# rgb_led.net
KiCad netlist of a schematic drawn in EAGLE
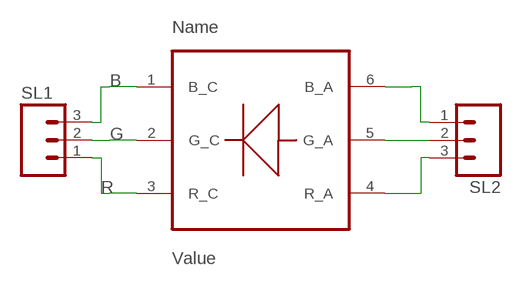
[diagram p0: schematic, sheet 1]

(export (version "E")
  (design (tool "Eeschema 10.0.6"))
  (components
    (comp (ref "SL1")
      (value "M03")
      (footprint "eagle-import:03P")
      (libsource (lib "eagle-import") (part "M03"))
    )
    (comp (ref "SL2")
      (value "M03")
      (footprint "eagle-import:03P")
      (libsource (lib "eagle-import") (part "M03"))
    )
    (comp (ref "U$2")
      (value "RGB_SMD_3W")
      (footprint "eagle-import:RGB_SMD_6PIN")
      (libsource (lib "eagle-import") (part "RGB_SMD_3W"))
    )
  )
  (nets
    (net (code "1") (name "/B") (class "Default")
      (node (ref "SL1") (pin "3") (pinfunction "3_3") (pintype "passive"))
      (node (ref "U$2") (pin "1") (pinfunction "B_C_1") (pintype "passive"))
    )
    (net (code "2") (name "/G") (class "Default")
      (node (ref "SL1") (pin "2") (pinfunction "2_2") (pintype "passive"))
      (node (ref "U$2") (pin "2") (pinfunction "G_C_2") (pintype "passive"))
    )
    (net (code "3") (name "/R") (class "Default")
      (node (ref "SL1") (pin "1") (pinfunction "1_1") (pintype "passive"))
      (node (ref "U$2") (pin "3") (pinfunction "R_C_3") (pintype "passive"))
    )
    (net (code "4") (name "Net-(U$2-B_A)") (class "Default")
      (node (ref "SL2") (pin "1") (pinfunction "1_1") (pintype "passive"))
      (node (ref "U$2") (pin "6") (pinfunction "B_A_6") (pintype "passive"))
    )
    (net (code "5") (name "Net-(U$2-G_A)") (class "Default")
      (node (ref "SL2") (pin "2") (pinfunction "2_2") (pintype "passive"))
      (node (ref "U$2") (pin "5") (pinfunction "G_A_5") (pintype "passive"))
    )
    (net (code "6") (name "Net-(U$2-R_A)") (class "Default")
      (node (ref "SL2") (pin "3") (pinfunction "3_3") (pintype "passive"))
      (node (ref "U$2") (pin "4") (pinfunction "R_A_4") (pintype "passive"))
    )
  )
)
